# IDS_ADC.net
KiCad netlist of a schematic drawn in EAGLE
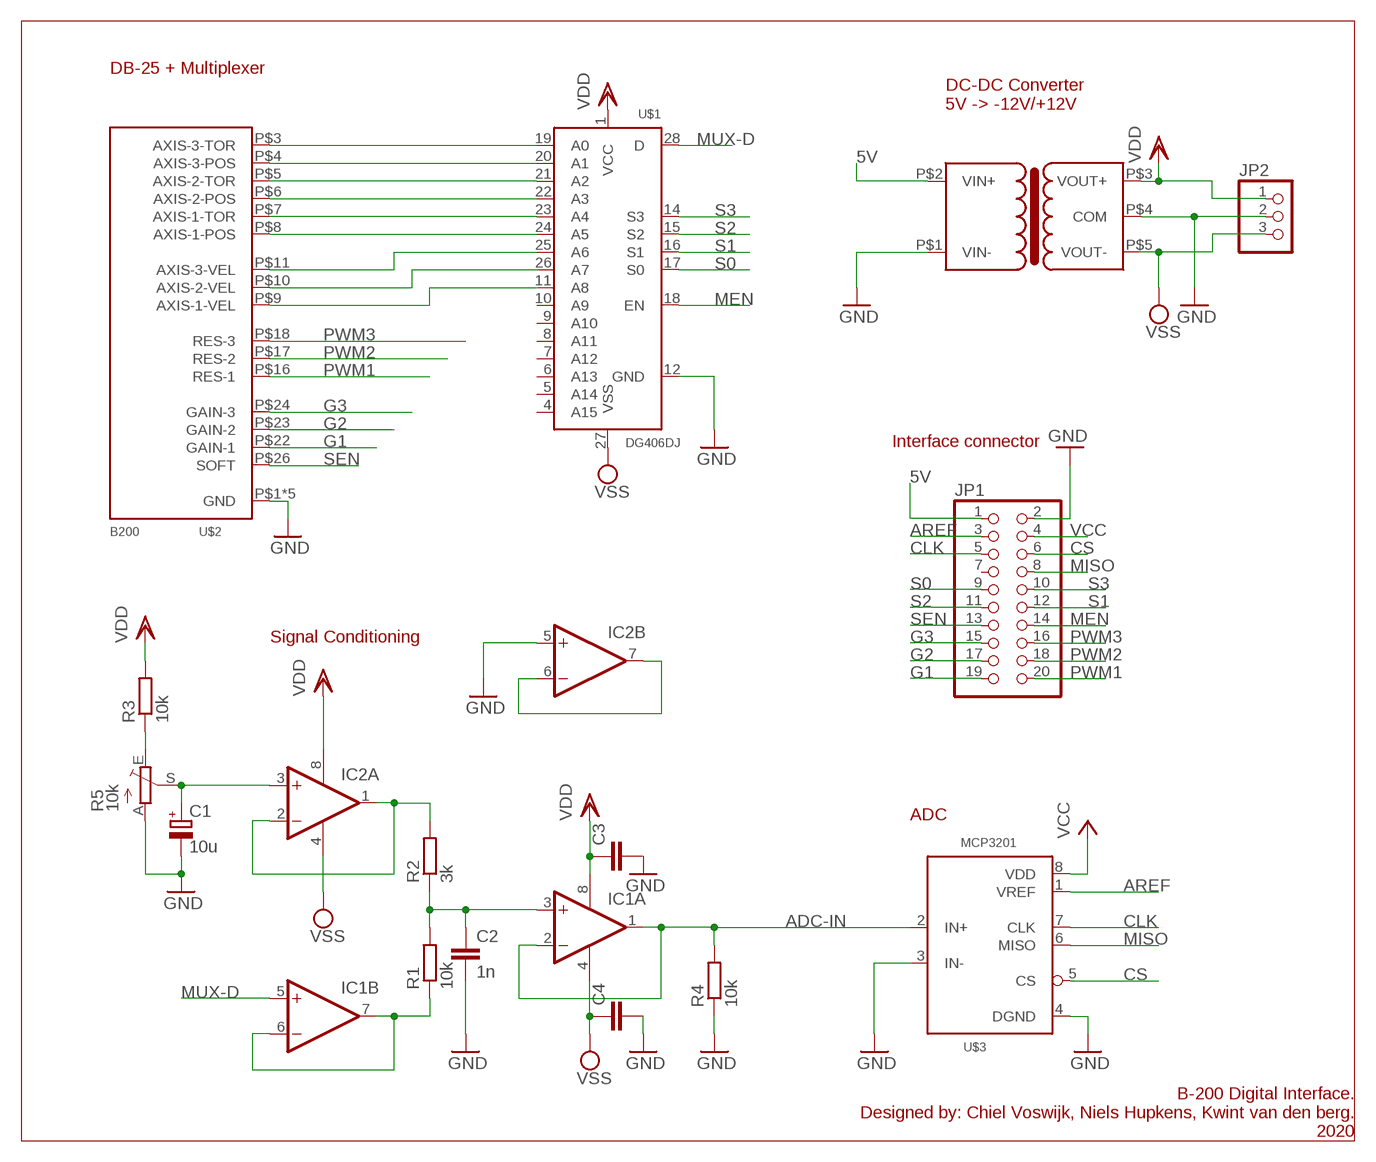
[diagram p0: schematic, sheet 1]

(export (version "E")
  (design (tool "Eeschema 10.0.6"))
  (components
    (comp (ref "C1")
      (value "10u")
      (footprint "eagle-import:E2,5-7")
      (libsource (lib "eagle-import") (part "CPOL-EUE2.5-7"))
    )
    (comp (ref "C2")
      (value "1n")
      (footprint "eagle-import:C1206")
      (libsource (lib "eagle-import") (part "C-EUC1206"))
    )
    (comp (ref "C3")
      (value "C-EUC1206")
      (footprint "eagle-import:C1206")
      (libsource (lib "eagle-import") (part "C-EUC1206"))
    )
    (comp (ref "C4")
      (value "C-EUC1206")
      (footprint "eagle-import:C1206")
      (libsource (lib "eagle-import") (part "C-EUC1206"))
    )
    (comp (ref "IC1")
      (value "NE5532N")
      (footprint "eagle-import:DIL08")
      (libsource (lib "eagle-import") (part "NE5532N"))
    )
    (comp (ref "IC2")
      (value "NE5532N")
      (footprint "eagle-import:DIL08")
      (libsource (lib "eagle-import") (part "NE5532N"))
    )
    (comp (ref "JP1")
      (value "PINHD-2X10")
      (footprint "eagle-import:2X10")
      (libsource (lib "eagle-import") (part "PINHD-2X10"))
    )
    (comp (ref "JP2")
      (value "PINHD-1X3")
      (footprint "eagle-import:1X03")
      (libsource (lib "eagle-import") (part "PINHD-1X3"))
    )
    (comp (ref "R1")
      (value "10k")
      (footprint "eagle-import:0207_7")
      (libsource (lib "eagle-import") (part "R-EU_0207/7"))
    )
    (comp (ref "R2")
      (value "3k")
      (footprint "eagle-import:0207_7")
      (libsource (lib "eagle-import") (part "R-EU_0207/7"))
    )
    (comp (ref "R3")
      (value "10k")
      (footprint "eagle-import:0207_7")
      (libsource (lib "eagle-import") (part "R-EU_0207/7"))
    )
    (comp (ref "R4")
      (value "10k")
      (footprint "eagle-import:0207_7")
      (libsource (lib "eagle-import") (part "R-EU_0207/7"))
    )
    (comp (ref "R5")
      (value "10k")
      (footprint "eagle-import:RJ9W")
      (libsource (lib "eagle-import") (part "TRIM_EU-RJ9W"))
    )
    (comp (ref "U$1")
      (value "DG406DJ")
      (footprint "eagle-import:DIL28-6")
      (libsource (lib "eagle-import") (part "DG406DJ"))
    )
    (comp (ref "U$2")
      (value "B200")
      (footprint "eagle-import:PARALLEL")
      (libsource (lib "eagle-import") (part "B200"))
    )
    (comp (ref "U$3")
      (value "MCP3201")
      (footprint "eagle-import:DIL08")
      (libsource (lib "eagle-import") (part "MCP3201"))
    )
    (comp (ref "U$4")
      (value "TRACO-DR-NE")
      (footprint "eagle-import:TRACO-DCDC-SIP6")
      (libsource (lib "eagle-import") (part "TRACO-DR-NE"))
    )
  )
  (nets
    (net (code "1") (name "/5V") (class "Default")
      (node (ref "JP1") (pin "1") (pinfunction "1_1") (pintype "passive"))
      (node (ref "U$4") (pin "P$2") (pinfunction "VIN+_P$2") (pintype "bidirectional"))
    )
    (net (code "2") (name "/ADC-IN") (class "Default")
      (node (ref "IC1") (pin "1") (pinfunction "OUT_1") (pintype "output"))
      (node (ref "IC1") (pin "2") (pinfunction "-IN_2") (pintype "input"))
      (node (ref "R4") (pin "2") (pinfunction "2_2") (pintype "passive"))
      (node (ref "U$3") (pin "2") (pinfunction "IN+_2") (pintype "input"))
    )
    (net (code "3") (name "/AREF") (class "Default")
      (node (ref "JP1") (pin "3") (pinfunction "3_3") (pintype "passive"))
      (node (ref "U$3") (pin "1") (pinfunction "VREF_1") (pintype "bidirectional"))
    )
    (net (code "4") (name "/CLK") (class "Default")
      (node (ref "JP1") (pin "5") (pinfunction "5_5") (pintype "passive"))
      (node (ref "U$3") (pin "7") (pinfunction "CLK_7") (pintype "bidirectional"))
    )
    (net (code "5") (name "/CS") (class "Default")
      (node (ref "JP1") (pin "6") (pinfunction "6_6") (pintype "passive"))
      (node (ref "U$3") (pin "5") (pinfunction "CS_5") (pintype "bidirectional"))
    )
    (net (code "6") (name "/G1") (class "Default")
      (node (ref "JP1") (pin "19") (pinfunction "19_19") (pintype "passive"))
      (node (ref "U$2") (pin "P$22") (pinfunction "GAIN-1_P$22") (pintype "output"))
    )
    (net (code "7") (name "/G2") (class "Default")
      (node (ref "JP1") (pin "17") (pinfunction "17_17") (pintype "passive"))
      (node (ref "U$2") (pin "P$23") (pinfunction "GAIN-2_P$23") (pintype "output"))
    )
    (net (code "8") (name "/G3") (class "Default")
      (node (ref "JP1") (pin "15") (pinfunction "15_15") (pintype "passive"))
      (node (ref "U$2") (pin "P$24") (pinfunction "GAIN-3_P$24") (pintype "output"))
    )
    (net (code "9") (name "/MEN") (class "Default")
      (node (ref "JP1") (pin "14") (pinfunction "14_14") (pintype "passive"))
      (node (ref "U$1") (pin "18") (pinfunction "EN_18") (pintype "input"))
    )
    (net (code "10") (name "/MISO") (class "Default")
      (node (ref "JP1") (pin "8") (pinfunction "8_8") (pintype "passive"))
      (node (ref "U$3") (pin "6") (pinfunction "MISO_6") (pintype "bidirectional"))
    )
    (net (code "11") (name "/MUX-D") (class "Default")
      (node (ref "IC1") (pin "5") (pinfunction "+IN_5") (pintype "input"))
      (node (ref "U$1") (pin "28") (pinfunction "D_28") (pintype "bidirectional"))
    )
    (net (code "12") (name "/PWM1") (class "Default")
      (node (ref "JP1") (pin "20") (pinfunction "20_20") (pintype "passive"))
      (node (ref "U$2") (pin "P$16") (pinfunction "RES-1_P$16") (pintype "output"))
    )
    (net (code "13") (name "/PWM2") (class "Default")
      (node (ref "JP1") (pin "18") (pinfunction "18_18") (pintype "passive"))
      (node (ref "U$2") (pin "P$17") (pinfunction "RES-2_P$17") (pintype "output"))
    )
    (net (code "14") (name "/PWM3") (class "Default")
      (node (ref "JP1") (pin "16") (pinfunction "16_16") (pintype "passive"))
      (node (ref "U$2") (pin "P$18") (pinfunction "RES-3_P$18") (pintype "output"))
    )
    (net (code "15") (name "/S0") (class "Default")
      (node (ref "JP1") (pin "9") (pinfunction "9_9") (pintype "passive"))
      (node (ref "U$1") (pin "17") (pinfunction "S0_17") (pintype "input"))
    )
    (net (code "16") (name "/S1") (class "Default")
      (node (ref "JP1") (pin "12") (pinfunction "12_12") (pintype "passive"))
      (node (ref "U$1") (pin "16") (pinfunction "S1_16") (pintype "input"))
    )
    (net (code "17") (name "/S2") (class "Default")
      (node (ref "JP1") (pin "11") (pinfunction "11_11") (pintype "passive"))
      (node (ref "U$1") (pin "15") (pinfunction "S2_15") (pintype "input"))
    )
    (net (code "18") (name "/S3") (class "Default")
      (node (ref "JP1") (pin "10") (pinfunction "10_10") (pintype "passive"))
      (node (ref "U$1") (pin "14") (pinfunction "S3_14") (pintype "input"))
    )
    (net (code "19") (name "/SEN") (class "Default")
      (node (ref "JP1") (pin "13") (pinfunction "13_13") (pintype "passive"))
      (node (ref "U$2") (pin "P$26") (pinfunction "SOFT_P$26") (pintype "output"))
    )
    (net (code "20") (name "GND") (class "Default")
      (node (ref "C1") (pin "-") (pinfunction "-_-") (pintype "passive"))
      (node (ref "C2") (pin "2") (pinfunction "2_2") (pintype "passive"))
      (node (ref "C3") (pin "2") (pinfunction "2_2") (pintype "passive"))
      (node (ref "C4") (pin "2") (pinfunction "2_2") (pintype "passive"))
      (node (ref "IC2") (pin "5") (pinfunction "+IN_5") (pintype "input"))
      (node (ref "JP1") (pin "2") (pinfunction "2_2") (pintype "passive"))
      (node (ref "JP2") (pin "2") (pinfunction "2_2") (pintype "passive"))
      (node (ref "R4") (pin "1") (pinfunction "1_1") (pintype "passive"))
      (node (ref "R5") (pin "A") (pinfunction "A_A") (pintype "passive"))
      (node (ref "U$1") (pin "12") (pinfunction "GND_12") (pintype "open_collector"))
      (node (ref "U$2") (pin "P$1") (pinfunction "GND_P$1") (pintype "output"))
      (node (ref "U$2") (pin "P$19") (pinfunction "GND_P$19") (pintype "output"))
      (node (ref "U$2") (pin "P$2") (pinfunction "GND_P$2") (pintype "output"))
      (node (ref "U$2") (pin "P$20") (pinfunction "GND_P$20") (pintype "output"))
      (node (ref "U$2") (pin "P$21") (pinfunction "GND_P$21") (pintype "output"))
      (node (ref "U$3") (pin "3") (pinfunction "IN-_3") (pintype "input"))
      (node (ref "U$3") (pin "4") (pinfunction "DGND_4") (pintype "power_in"))
      (node (ref "U$4") (pin "P$1") (pinfunction "VIN-_P$1") (pintype "bidirectional"))
      (node (ref "U$4") (pin "P$4") (pinfunction "COM_P$4") (pintype "bidirectional"))
    )
    (net (code "21") (name "Net-(IC1A-+IN)") (class "Default")
      (node (ref "C2") (pin "1") (pinfunction "1_1") (pintype "passive"))
      (node (ref "IC1") (pin "3") (pinfunction "+IN_3") (pintype "input"))
      (node (ref "R1") (pin "2") (pinfunction "2_2") (pintype "passive"))
      (node (ref "R2") (pin "1") (pinfunction "1_1") (pintype "passive"))
    )
    (net (code "22") (name "Net-(IC1B--IN)") (class "Default")
      (node (ref "IC1") (pin "6") (pinfunction "-IN_6") (pintype "input"))
      (node (ref "IC1") (pin "7") (pinfunction "OUT_7") (pintype "output"))
      (node (ref "R1") (pin "1") (pinfunction "1_1") (pintype "passive"))
    )
    (net (code "23") (name "Net-(IC2A-+IN)") (class "Default")
      (node (ref "C1") (pin "+") (pinfunction "+_+") (pintype "passive"))
      (node (ref "IC2") (pin "3") (pinfunction "+IN_3") (pintype "input"))
      (node (ref "R5") (pin "S") (pinfunction "S_S") (pintype "passive"))
    )
    (net (code "24") (name "Net-(IC2A--IN)") (class "Default")
      (node (ref "IC2") (pin "1") (pinfunction "OUT_1") (pintype "output"))
      (node (ref "IC2") (pin "2") (pinfunction "-IN_2") (pintype "input"))
      (node (ref "R2") (pin "2") (pinfunction "2_2") (pintype "passive"))
    )
    (net (code "25") (name "Net-(IC2B--IN)") (class "Default")
      (node (ref "IC2") (pin "6") (pinfunction "-IN_6") (pintype "input"))
      (node (ref "IC2") (pin "7") (pinfunction "OUT_7") (pintype "output"))
    )
    (net (code "26") (name "Net-(R3-Pad1)") (class "Default")
      (node (ref "R3") (pin "1") (pinfunction "1_1") (pintype "passive"))
      (node (ref "R5") (pin "E") (pinfunction "E_E") (pintype "passive"))
    )
    (net (code "27") (name "Net-(U$1-A0)") (class "Default")
      (node (ref "U$1") (pin "19") (pinfunction "A0_19") (pintype "bidirectional"))
      (node (ref "U$2") (pin "P$3") (pinfunction "AXIS-3-TOR_P$3") (pintype "output"))
    )
    (net (code "28") (name "Net-(U$1-A1)") (class "Default")
      (node (ref "U$1") (pin "20") (pinfunction "A1_20") (pintype "bidirectional"))
      (node (ref "U$2") (pin "P$4") (pinfunction "AXIS-3-POS_P$4") (pintype "output"))
    )
    (net (code "29") (name "Net-(U$1-A2)") (class "Default")
      (node (ref "U$1") (pin "21") (pinfunction "A2_21") (pintype "bidirectional"))
      (node (ref "U$2") (pin "P$5") (pinfunction "AXIS-2-TOR_P$5") (pintype "output"))
    )
    (net (code "30") (name "Net-(U$1-A3)") (class "Default")
      (node (ref "U$1") (pin "22") (pinfunction "A3_22") (pintype "bidirectional"))
      (node (ref "U$2") (pin "P$6") (pinfunction "AXIS-2-POS_P$6") (pintype "output"))
    )
    (net (code "31") (name "Net-(U$1-A4)") (class "Default")
      (node (ref "U$1") (pin "23") (pinfunction "A4_23") (pintype "bidirectional"))
      (node (ref "U$2") (pin "P$7") (pinfunction "AXIS-1-TOR_P$7") (pintype "output"))
    )
    (net (code "32") (name "Net-(U$1-A5)") (class "Default")
      (node (ref "U$1") (pin "24") (pinfunction "A5_24") (pintype "bidirectional"))
      (node (ref "U$2") (pin "P$8") (pinfunction "AXIS-1-POS_P$8") (pintype "output"))
    )
    (net (code "33") (name "Net-(U$1-A6)") (class "Default")
      (node (ref "U$1") (pin "25") (pinfunction "A6_25") (pintype "bidirectional"))
      (node (ref "U$2") (pin "P$11") (pinfunction "AXIS-3-VEL_P$11") (pintype "output"))
    )
    (net (code "34") (name "Net-(U$1-A7)") (class "Default")
      (node (ref "U$1") (pin "26") (pinfunction "A7_26") (pintype "bidirectional"))
      (node (ref "U$2") (pin "P$10") (pinfunction "AXIS-2-VEL_P$10") (pintype "output"))
    )
    (net (code "35") (name "Net-(U$1-A8)") (class "Default")
      (node (ref "U$1") (pin "11") (pinfunction "A8_11") (pintype "bidirectional"))
      (node (ref "U$2") (pin "P$9") (pinfunction "AXIS-1-VEL_P$9") (pintype "output"))
    )
    (net (code "36") (name "VCC") (class "Default")
      (node (ref "JP1") (pin "4") (pinfunction "4_4") (pintype "passive"))
      (node (ref "U$3") (pin "8") (pinfunction "VDD_8") (pintype "power_in"))
    )
    (net (code "37") (name "VDD") (class "Default")
      (node (ref "C3") (pin "1") (pinfunction "1_1") (pintype "passive"))
      (node (ref "IC1") (pin "8") (pinfunction "V+_8") (pintype "power_in"))
      (node (ref "IC2") (pin "8") (pinfunction "V+_8") (pintype "power_in"))
      (node (ref "JP2") (pin "1") (pinfunction "1_1") (pintype "passive"))
      (node (ref "R3") (pin "2") (pinfunction "2_2") (pintype "passive"))
      (node (ref "U$1") (pin "1") (pinfunction "VCC_1") (pintype "power_in"))
      (node (ref "U$4") (pin "P$3") (pinfunction "VOUT+_P$3") (pintype "bidirectional"))
    )
    (net (code "38") (name "VSS") (class "Default")
      (node (ref "C4") (pin "1") (pinfunction "1_1") (pintype "passive"))
      (node (ref "IC1") (pin "4") (pinfunction "V-_4") (pintype "power_in"))
      (node (ref "IC2") (pin "4") (pinfunction "V-_4") (pintype "power_in"))
      (node (ref "JP2") (pin "3") (pinfunction "3_3") (pintype "passive"))
      (node (ref "U$1") (pin "27") (pinfunction "VSS_27") (pintype "open_collector"))
      (node (ref "U$4") (pin "P$5") (pinfunction "VOUT-_P$5") (pintype "bidirectional"))
    )
    (net (code "39") (name "unconnected-(JP1-Pad7)") (class "Default")
      (node (ref "JP1") (pin "7") (pinfunction "7_7") (pintype "passive"))
    )
    (net (code "40") (name "unconnected-(U$1-A9-Pad10)") (class "Default")
      (node (ref "U$1") (pin "10") (pinfunction "A9_10") (pintype "bidirectional"))
    )
    (net (code "41") (name "unconnected-(U$1-A10-Pad9)") (class "Default")
      (node (ref "U$1") (pin "9") (pinfunction "A10_9") (pintype "bidirectional"))
    )
    (net (code "42") (name "unconnected-(U$1-A11-Pad8)") (class "Default")
      (node (ref "U$1") (pin "8") (pinfunction "A11_8") (pintype "bidirectional"))
    )
    (net (code "43") (name "unconnected-(U$1-A12-Pad7)") (class "Default")
      (node (ref "U$1") (pin "7") (pinfunction "A12_7") (pintype "bidirectional"))
    )
    (net (code "44") (name "unconnected-(U$1-A13-Pad6)") (class "Default")
      (node (ref "U$1") (pin "6") (pinfunction "A13_6") (pintype "bidirectional"))
    )
    (net (code "45") (name "unconnected-(U$1-A14-Pad5)") (class "Default")
      (node (ref "U$1") (pin "5") (pinfunction "A14_5") (pintype "bidirectional"))
    )
    (net (code "46") (name "unconnected-(U$1-A15-Pad4)") (class "Default")
      (node (ref "U$1") (pin "4") (pinfunction "A15_4") (pintype "bidirectional"))
    )
  )
)
